# init.net
KiCad netlist of a schematic drawn in EAGLE
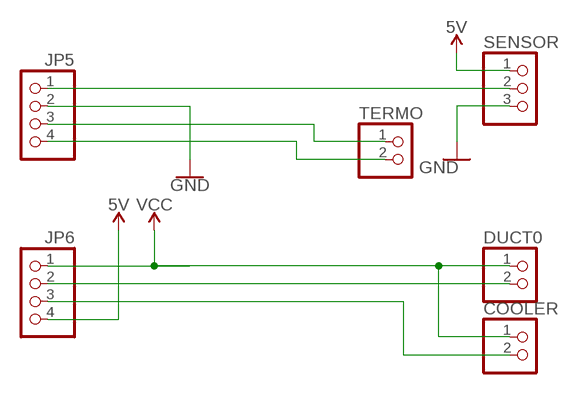
[diagram p0: schematic, sheet 1]

(export (version "E")
  (design (tool "Eeschema 10.0.6"))
  (components
    (comp (ref "COOLER")
      (value "PINHD-1X2")
      (footprint "eagle-import:1X02")
      (libsource (lib "eagle-import") (part "PINHD-1X2"))
    )
    (comp (ref "DUCT0")
      (value "PINHD-1X2")
      (footprint "eagle-import:1X02")
      (libsource (lib "eagle-import") (part "PINHD-1X2"))
    )
    (comp (ref "JP5")
      (value "PINHD-1X4")
      (footprint "eagle-import:1X04")
      (libsource (lib "eagle-import") (part "PINHD-1X4"))
    )
    (comp (ref "JP6")
      (value "PINHD-1X4")
      (footprint "eagle-import:1X04")
      (libsource (lib "eagle-import") (part "PINHD-1X4"))
    )
    (comp (ref "SENSOR")
      (value "PINHD-1X3")
      (footprint "eagle-import:1X03")
      (libsource (lib "eagle-import") (part "PINHD-1X3"))
    )
    (comp (ref "TERMO")
      (value "PINHD-1X2")
      (footprint "eagle-import:1X02")
      (libsource (lib "eagle-import") (part "PINHD-1X2"))
    )
  )
  (nets
    (net (code "1") (name "5V") (class "Default")
      (node (ref "JP6") (pin "4") (pinfunction "4_4") (pintype "passive"))
      (node (ref "SENSOR") (pin "1") (pinfunction "1_1") (pintype "passive"))
    )
    (net (code "2") (name "GND") (class "Default")
      (node (ref "JP5") (pin "2") (pinfunction "2_2") (pintype "passive"))
      (node (ref "SENSOR") (pin "3") (pinfunction "3_3") (pintype "passive"))
    )
    (net (code "3") (name "Net-(COOLER-Pad2)") (class "Default")
      (node (ref "COOLER") (pin "2") (pinfunction "2_2") (pintype "passive"))
      (node (ref "JP6") (pin "3") (pinfunction "3_3") (pintype "passive"))
    )
    (net (code "4") (name "Net-(DUCT0-Pad2)") (class "Default")
      (node (ref "DUCT0") (pin "2") (pinfunction "2_2") (pintype "passive"))
      (node (ref "JP6") (pin "2") (pinfunction "2_2") (pintype "passive"))
    )
    (net (code "5") (name "Net-(JP5-Pad1)") (class "Default")
      (node (ref "JP5") (pin "1") (pinfunction "1_1") (pintype "passive"))
      (node (ref "SENSOR") (pin "2") (pinfunction "2_2") (pintype "passive"))
    )
    (net (code "6") (name "Net-(JP5-Pad3)") (class "Default")
      (node (ref "JP5") (pin "3") (pinfunction "3_3") (pintype "passive"))
      (node (ref "TERMO") (pin "1") (pinfunction "1_1") (pintype "passive"))
    )
    (net (code "7") (name "Net-(JP5-Pad4)") (class "Default")
      (node (ref "JP5") (pin "4") (pinfunction "4_4") (pintype "passive"))
      (node (ref "TERMO") (pin "2") (pinfunction "2_2") (pintype "passive"))
    )
    (net (code "8") (name "VCC") (class "Default")
      (node (ref "COOLER") (pin "1") (pinfunction "1_1") (pintype "passive"))
      (node (ref "DUCT0") (pin "1") (pinfunction "1_1") (pintype "passive"))
      (node (ref "JP6") (pin "1") (pinfunction "1_1") (pintype "passive"))
    )
  )
)
